# Leds.net
KiCad netlist of a schematic drawn in Altium Designer
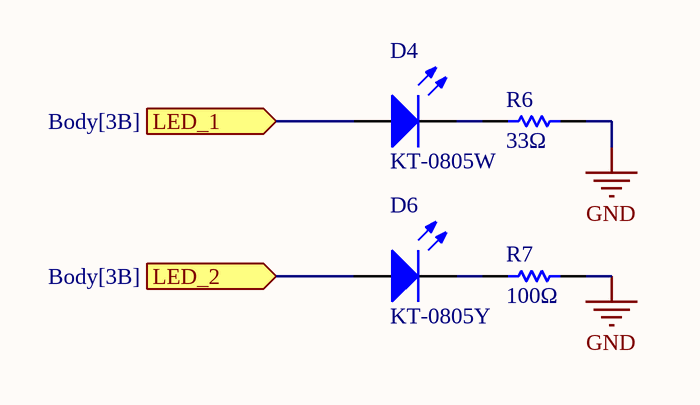
[diagram p0: Leds.SchDoc]

(export (version "E")
  (design (tool "Eeschema 10.0.6"))
  (components
    (comp (ref "D4")
      (value "KT-0805W")
      (footprint "LED0805")
      (description "0805 LED Indication - Discrete ROHS")
      (fields (field (name "MANUFACTURER") "Hubei KENTO Elec"))
      (libsource (lib "StandartComponents") (part "KT-0805W"))
    )
    (comp (ref "D6")
      (value "KT-0805Y")
      (footprint "LED0805")
      (description "Yellow 0805 LED Indication - Discrete ROHS")
      (fields (field (name "MANUFACTURER") "Hubei KENTO Elec"))
      (libsource (lib "StandartComponents") (part "KT-0805Y"))
    )
    (comp (ref "R6")
      (value "33Ω")
      (footprint "RES0805")
      (description "125mW Thick Film Resistors 150V ±1% ±200ppm/℃ 33Ω 0805 Chip Resistor - Surface Mount ROHS")
      (fields (field (name "PART NUMBER") "0805W8F330JT5E"))
      (libsource (lib "StandartComponents") (part "0805W8F330JT5E"))
    )
    (comp (ref "R7")
      (value "100Ω")
      (footprint "RES0805")
      (description "125mW Thick Film Resistors 150V ±100ppm/℃ ±1% 100Ω 0805 Chip Resistor - Surface Mount ROHS")
      (fields (field (name "MANUFACTURER_PART_NUMBER") "0805W8F1000T5E"))
      (libsource (lib "StandartComponents") (part "0805W8F1000T5E"))
    )
  )
  (nets
    (net (code "1") (name "/LED_1") (class "Default")
      (node (ref "D4") (pin "A") (pinfunction "A_A") (pintype "passive"))
    )
    (net (code "2") (name "/LED_2") (class "Default")
      (node (ref "D6") (pin "A") (pinfunction "A_A") (pintype "passive"))
    )
    (net (code "3") (name "GND") (class "Default")
      (node (ref "R6") (pin "2") (pinfunction "2_2") (pintype "passive"))
      (node (ref "R7") (pin "2") (pinfunction "2_2") (pintype "passive"))
    )
    (net (code "4") (name "Net-(D4-PadK)") (class "Default")
      (node (ref "D4") (pin "K") (pinfunction "K_K") (pintype "passive"))
      (node (ref "R6") (pin "1") (pinfunction "1_1") (pintype "passive"))
    )
    (net (code "5") (name "Net-(D6-PadK)") (class "Default")
      (node (ref "D6") (pin "K") (pinfunction "K_K") (pintype "passive"))
      (node (ref "R7") (pin "1") (pinfunction "1_1") (pintype "passive"))
    )
  )
)
